# ASIC_1.net
KiCad netlist of a schematic drawn in Altium Designer
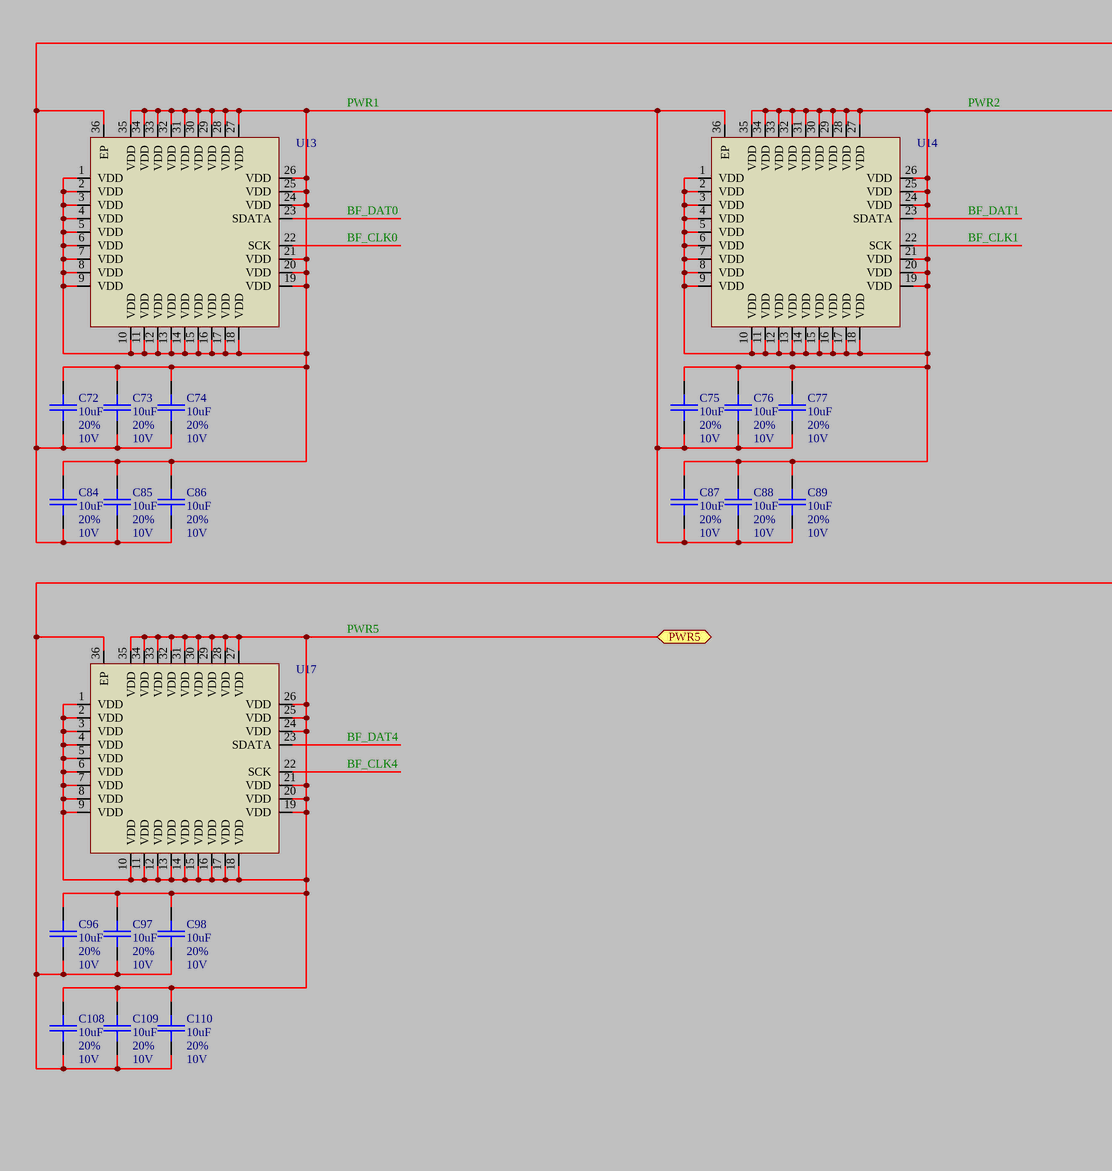
[diagram p0: ASIC_1.SchDoc, left]
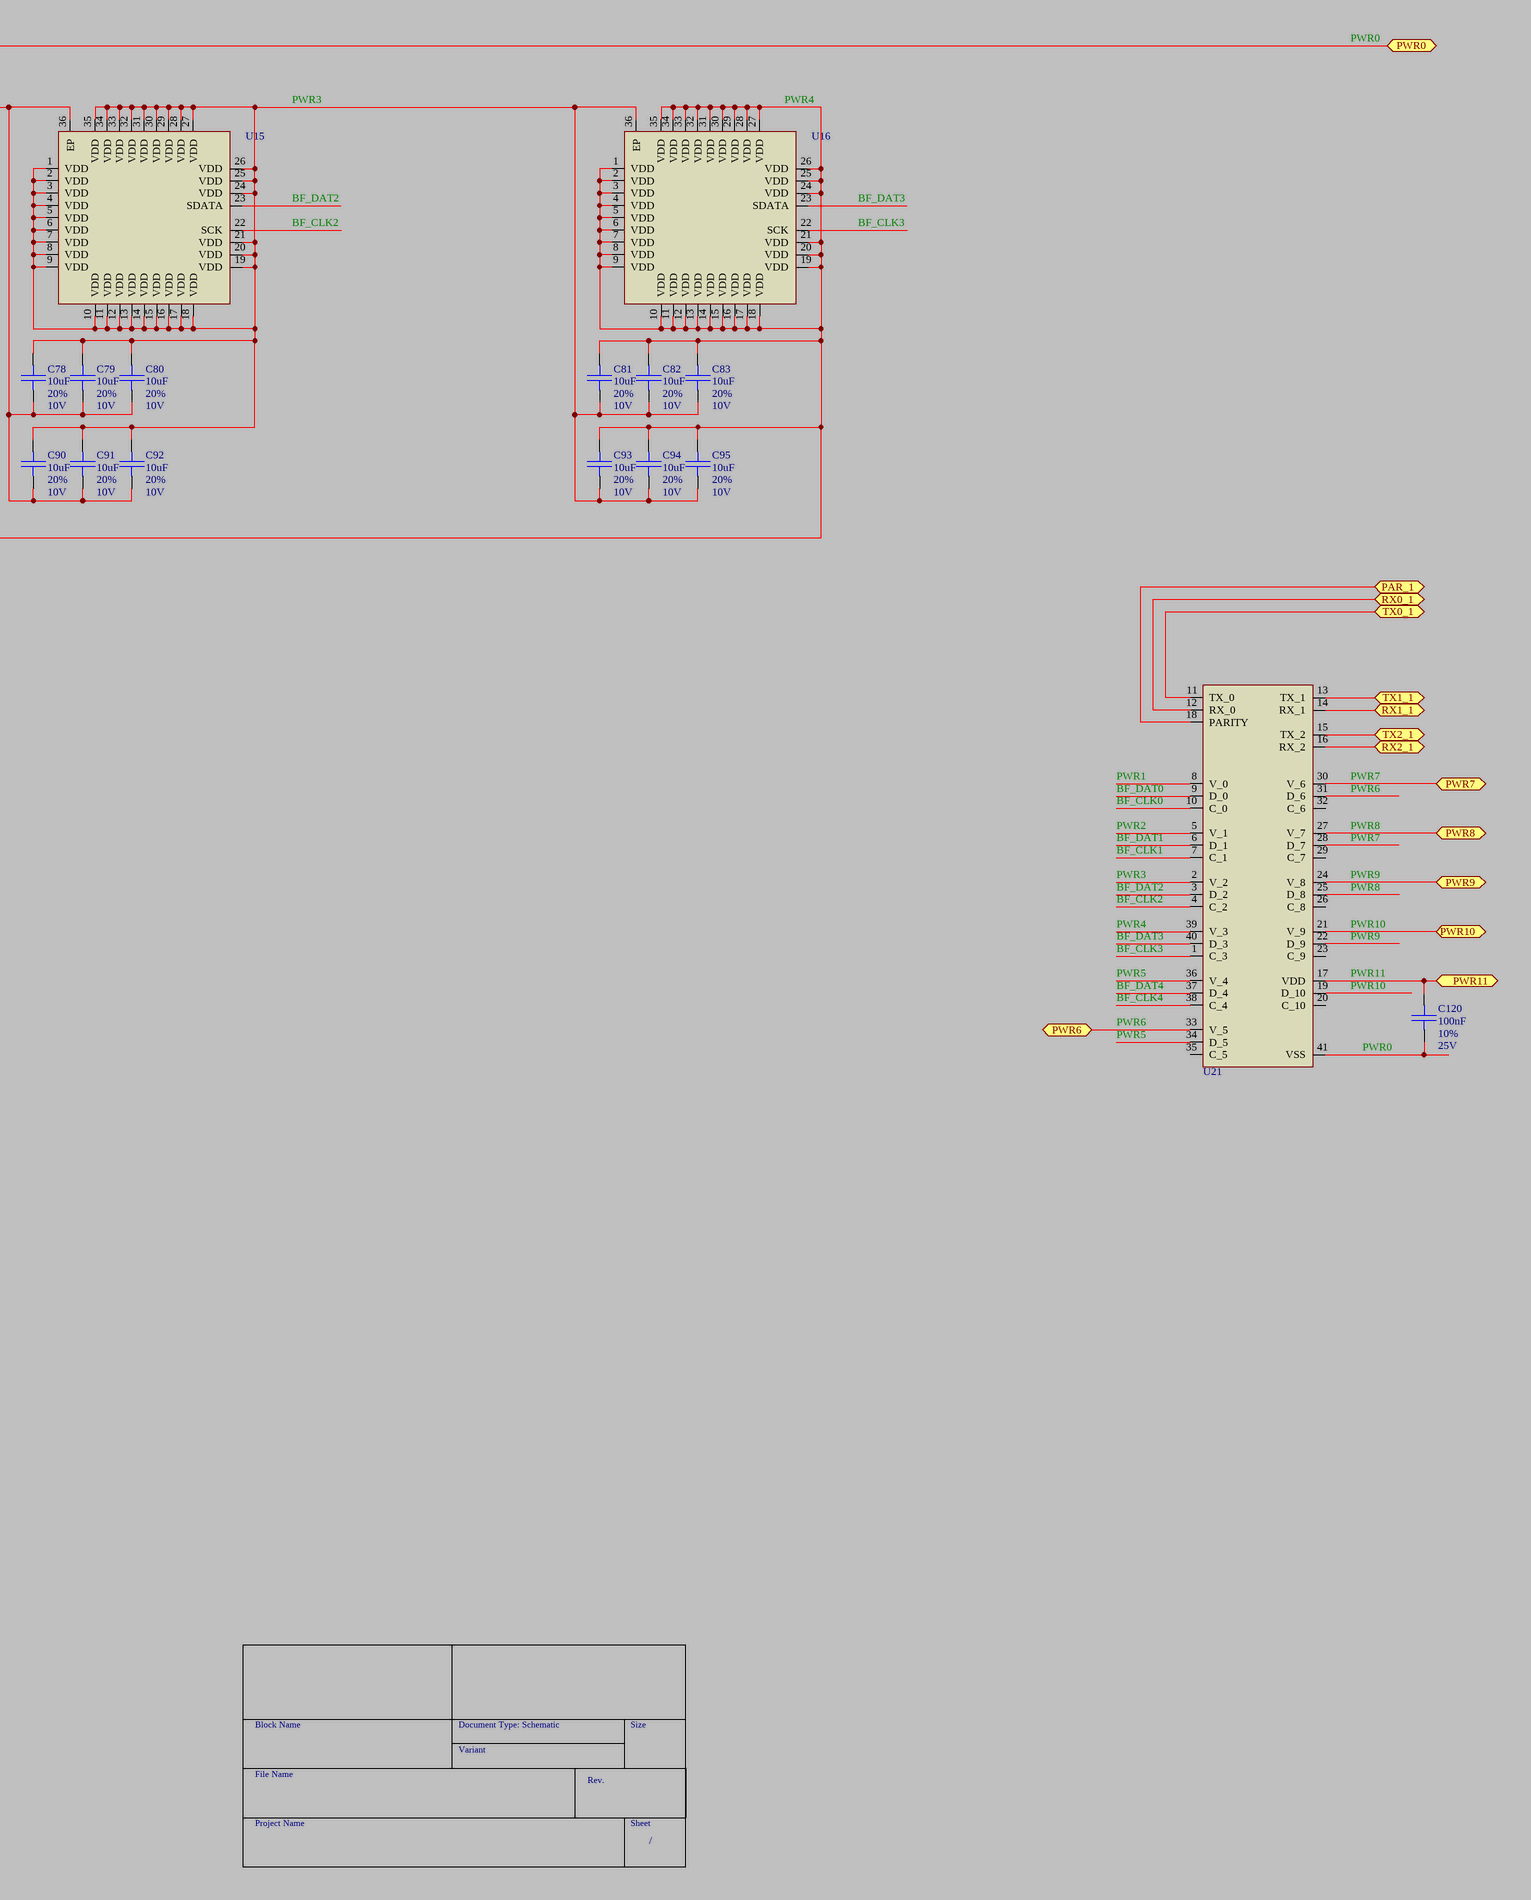
[diagram p1: ASIC_1.SchDoc, right]

(export (version "E")
  (design (tool "Eeschema 10.0.6"))
  (components
    (comp (ref "C72")
      (value "C")
      (footprint "SMD_0402_CAPC1005X70N")
      (fields
        (field (name "DB_PART_NUMBER") "CAP000047481")
        (field (name "DB_VALUE") "10uF")
        (field (name "DB_TOLERANCE") "20%")
        (field (name "DB_VOLTAGE") "10V")
        (field (name "DB_MANUFACTURER_PART") "SAMSUNG    CL05A106MP5NUNC")
        (field (name "DB_APPROVED_BY") "VSN")
      )
      (libsource (lib "Database_Libs1") (part "C"))
    )
    (comp (ref "C73")
      (value "C")
      (footprint "SMD_0402_CAPC1005X70N")
      (fields
        (field (name "DB_PART_NUMBER") "CAP000047481")
        (field (name "DB_VALUE") "10uF")
        (field (name "DB_TOLERANCE") "20%")
        (field (name "DB_VOLTAGE") "10V")
        (field (name "DB_MANUFACTURER_PART") "SAMSUNG    CL05A106MP5NUNC")
        (field (name "DB_APPROVED_BY") "VSN")
      )
      (libsource (lib "Database_Libs1") (part "C"))
    )
    (comp (ref "C74")
      (value "C")
      (footprint "SMD_0402_CAPC1005X70N")
      (fields
        (field (name "DB_PART_NUMBER") "CAP000047481")
        (field (name "DB_VALUE") "10uF")
        (field (name "DB_TOLERANCE") "20%")
        (field (name "DB_VOLTAGE") "10V")
        (field (name "DB_MANUFACTURER_PART") "SAMSUNG    CL05A106MP5NUNC")
        (field (name "DB_APPROVED_BY") "VSN")
      )
      (libsource (lib "Database_Libs1") (part "C"))
    )
    (comp (ref "C75")
      (value "C")
      (footprint "SMD_0402_CAPC1005X70N")
      (fields
        (field (name "DB_PART_NUMBER") "CAP000047481")
        (field (name "DB_VALUE") "10uF")
        (field (name "DB_TOLERANCE") "20%")
        (field (name "DB_VOLTAGE") "10V")
        (field (name "DB_MANUFACTURER_PART") "SAMSUNG    CL05A106MP5NUNC")
        (field (name "DB_APPROVED_BY") "VSN")
      )
      (libsource (lib "Database_Libs1") (part "C"))
    )
    (comp (ref "C76")
      (value "C")
      (footprint "SMD_0402_CAPC1005X70N")
      (fields
        (field (name "DB_PART_NUMBER") "CAP000047481")
        (field (name "DB_VALUE") "10uF")
        (field (name "DB_TOLERANCE") "20%")
        (field (name "DB_VOLTAGE") "10V")
        (field (name "DB_MANUFACTURER_PART") "SAMSUNG    CL05A106MP5NUNC")
        (field (name "DB_APPROVED_BY") "VSN")
      )
      (libsource (lib "Database_Libs1") (part "C"))
    )
    (comp (ref "C77")
      (value "C")
      (footprint "SMD_0402_CAPC1005X70N")
      (fields
        (field (name "DB_PART_NUMBER") "CAP000047481")
        (field (name "DB_VALUE") "10uF")
        (field (name "DB_TOLERANCE") "20%")
        (field (name "DB_VOLTAGE") "10V")
        (field (name "DB_MANUFACTURER_PART") "SAMSUNG    CL05A106MP5NUNC")
        (field (name "DB_APPROVED_BY") "VSN")
      )
      (libsource (lib "Database_Libs1") (part "C"))
    )
    (comp (ref "C78")
      (value "C")
      (footprint "SMD_0402_CAPC1005X70N")
      (fields
        (field (name "DB_PART_NUMBER") "CAP000047481")
        (field (name "DB_VALUE") "10uF")
        (field (name "DB_TOLERANCE") "20%")
        (field (name "DB_VOLTAGE") "10V")
        (field (name "DB_MANUFACTURER_PART") "SAMSUNG    CL05A106MP5NUNC")
        (field (name "DB_APPROVED_BY") "VSN")
      )
      (libsource (lib "Database_Libs1") (part "C"))
    )
    (comp (ref "C79")
      (value "C")
      (footprint "SMD_0402_CAPC1005X70N")
      (fields
        (field (name "DB_PART_NUMBER") "CAP000047481")
        (field (name "DB_VALUE") "10uF")
        (field (name "DB_TOLERANCE") "20%")
        (field (name "DB_VOLTAGE") "10V")
        (field (name "DB_MANUFACTURER_PART") "SAMSUNG    CL05A106MP5NUNC")
        (field (name "DB_APPROVED_BY") "VSN")
      )
      (libsource (lib "Database_Libs1") (part "C"))
    )
    (comp (ref "C80")
      (value "C")
      (footprint "SMD_0402_CAPC1005X70N")
      (fields
        (field (name "DB_PART_NUMBER") "CAP000047481")
        (field (name "DB_VALUE") "10uF")
        (field (name "DB_TOLERANCE") "20%")
        (field (name "DB_VOLTAGE") "10V")
        (field (name "DB_MANUFACTURER_PART") "SAMSUNG    CL05A106MP5NUNC")
        (field (name "DB_APPROVED_BY") "VSN")
      )
      (libsource (lib "Database_Libs1") (part "C"))
    )
    (comp (ref "C81")
      (value "C")
      (footprint "SMD_0402_CAPC1005X70N")
      (fields
        (field (name "DB_PART_NUMBER") "CAP000047481")
        (field (name "DB_VALUE") "10uF")
        (field (name "DB_TOLERANCE") "20%")
        (field (name "DB_VOLTAGE") "10V")
        (field (name "DB_MANUFACTURER_PART") "SAMSUNG    CL05A106MP5NUNC")
        (field (name "DB_APPROVED_BY") "VSN")
      )
      (libsource (lib "Database_Libs1") (part "C"))
    )
    (comp (ref "C82")
      (value "C")
      (footprint "SMD_0402_CAPC1005X70N")
      (fields
        (field (name "DB_PART_NUMBER") "CAP000047481")
        (field (name "DB_VALUE") "10uF")
        (field (name "DB_TOLERANCE") "20%")
        (field (name "DB_VOLTAGE") "10V")
        (field (name "DB_MANUFACTURER_PART") "SAMSUNG    CL05A106MP5NUNC")
        (field (name "DB_APPROVED_BY") "VSN")
      )
      (libsource (lib "Database_Libs1") (part "C"))
    )
    (comp (ref "C83")
      (value "C")
      (footprint "SMD_0402_CAPC1005X70N")
      (fields
        (field (name "DB_PART_NUMBER") "CAP000047481")
        (field (name "DB_VALUE") "10uF")
        (field (name "DB_TOLERANCE") "20%")
        (field (name "DB_VOLTAGE") "10V")
        (field (name "DB_MANUFACTURER_PART") "SAMSUNG    CL05A106MP5NUNC")
        (field (name "DB_APPROVED_BY") "VSN")
      )
      (libsource (lib "Database_Libs1") (part "C"))
    )
    (comp (ref "C84")
      (value "C")
      (footprint "SMD_0402_CAPC1005X70N")
      (fields
        (field (name "DB_PART_NUMBER") "CAP000047481")
        (field (name "DB_VALUE") "10uF")
        (field (name "DB_TOLERANCE") "20%")
        (field (name "DB_VOLTAGE") "10V")
        (field (name "DB_MANUFACTURER_PART") "SAMSUNG    CL05A106MP5NUNC")
        (field (name "DB_APPROVED_BY") "VSN")
      )
      (libsource (lib "Database_Libs1") (part "C"))
    )
    (comp (ref "C85")
      (value "C")
      (footprint "SMD_0402_CAPC1005X70N")
      (fields
        (field (name "DB_PART_NUMBER") "CAP000047481")
        (field (name "DB_VALUE") "10uF")
        (field (name "DB_TOLERANCE") "20%")
        (field (name "DB_VOLTAGE") "10V")
        (field (name "DB_MANUFACTURER_PART") "SAMSUNG    CL05A106MP5NUNC")
        (field (name "DB_APPROVED_BY") "VSN")
      )
      (libsource (lib "Database_Libs1") (part "C"))
    )
    (comp (ref "C86")
      (value "C")
      (footprint "SMD_0402_CAPC1005X70N")
      (fields
        (field (name "DB_PART_NUMBER") "CAP000047481")
        (field (name "DB_VALUE") "10uF")
        (field (name "DB_TOLERANCE") "20%")
        (field (name "DB_VOLTAGE") "10V")
        (field (name "DB_MANUFACTURER_PART") "SAMSUNG    CL05A106MP5NUNC")
        (field (name "DB_APPROVED_BY") "VSN")
      )
      (libsource (lib "Database_Libs1") (part "C"))
    )
    (comp (ref "C87")
      (value "C")
      (footprint "SMD_0402_CAPC1005X70N")
      (fields
        (field (name "DB_PART_NUMBER") "CAP000047481")
        (field (name "DB_VALUE") "10uF")
        (field (name "DB_TOLERANCE") "20%")
        (field (name "DB_VOLTAGE") "10V")
        (field (name "DB_MANUFACTURER_PART") "SAMSUNG    CL05A106MP5NUNC")
        (field (name "DB_APPROVED_BY") "VSN")
      )
      (libsource (lib "Database_Libs1") (part "C"))
    )
    (comp (ref "C88")
      (value "C")
      (footprint "SMD_0402_CAPC1005X70N")
      (fields
        (field (name "DB_PART_NUMBER") "CAP000047481")
        (field (name "DB_VALUE") "10uF")
        (field (name "DB_TOLERANCE") "20%")
        (field (name "DB_VOLTAGE") "10V")
        (field (name "DB_MANUFACTURER_PART") "SAMSUNG    CL05A106MP5NUNC")
        (field (name "DB_APPROVED_BY") "VSN")
      )
      (libsource (lib "Database_Libs1") (part "C"))
    )
    (comp (ref "C89")
      (value "C")
      (footprint "SMD_0402_CAPC1005X70N")
      (fields
        (field (name "DB_PART_NUMBER") "CAP000047481")
        (field (name "DB_VALUE") "10uF")
        (field (name "DB_TOLERANCE") "20%")
        (field (name "DB_VOLTAGE") "10V")
        (field (name "DB_MANUFACTURER_PART") "SAMSUNG    CL05A106MP5NUNC")
        (field (name "DB_APPROVED_BY") "VSN")
      )
      (libsource (lib "Database_Libs1") (part "C"))
    )
    (comp (ref "C90")
      (value "C")
      (footprint "SMD_0402_CAPC1005X70N")
      (fields
        (field (name "DB_PART_NUMBER") "CAP000047481")
        (field (name "DB_VALUE") "10uF")
        (field (name "DB_TOLERANCE") "20%")
        (field (name "DB_VOLTAGE") "10V")
        (field (name "DB_MANUFACTURER_PART") "SAMSUNG    CL05A106MP5NUNC")
        (field (name "DB_APPROVED_BY") "VSN")
      )
      (libsource (lib "Database_Libs1") (part "C"))
    )
    (comp (ref "C91")
      (value "C")
      (footprint "SMD_0402_CAPC1005X70N")
      (fields
        (field (name "DB_PART_NUMBER") "CAP000047481")
        (field (name "DB_VALUE") "10uF")
        (field (name "DB_TOLERANCE") "20%")
        (field (name "DB_VOLTAGE") "10V")
        (field (name "DB_MANUFACTURER_PART") "SAMSUNG    CL05A106MP5NUNC")
        (field (name "DB_APPROVED_BY") "VSN")
      )
      (libsource (lib "Database_Libs1") (part "C"))
    )
    (comp (ref "C92")
      (value "C")
      (footprint "SMD_0402_CAPC1005X70N")
      (fields
        (field (name "DB_PART_NUMBER") "CAP000047481")
        (field (name "DB_VALUE") "10uF")
        (field (name "DB_TOLERANCE") "20%")
        (field (name "DB_VOLTAGE") "10V")
        (field (name "DB_MANUFACTURER_PART") "SAMSUNG    CL05A106MP5NUNC")
        (field (name "DB_APPROVED_BY") "VSN")
      )
      (libsource (lib "Database_Libs1") (part "C"))
    )
    (comp (ref "C93")
      (value "C")
      (footprint "SMD_0402_CAPC1005X70N")
      (fields
        (field (name "DB_PART_NUMBER") "CAP000047481")
        (field (name "DB_VALUE") "10uF")
        (field (name "DB_TOLERANCE") "20%")
        (field (name "DB_VOLTAGE") "10V")
        (field (name "DB_MANUFACTURER_PART") "SAMSUNG    CL05A106MP5NUNC")
        (field (name "DB_APPROVED_BY") "VSN")
      )
      (libsource (lib "Database_Libs1") (part "C"))
    )
    (comp (ref "C94")
      (value "C")
      (footprint "SMD_0402_CAPC1005X70N")
      (fields
        (field (name "DB_PART_NUMBER") "CAP000047481")
        (field (name "DB_VALUE") "10uF")
        (field (name "DB_TOLERANCE") "20%")
        (field (name "DB_VOLTAGE") "10V")
        (field (name "DB_MANUFACTURER_PART") "SAMSUNG    CL05A106MP5NUNC")
        (field (name "DB_APPROVED_BY") "VSN")
      )
      (libsource (lib "Database_Libs1") (part "C"))
    )
    (comp (ref "C95")
      (value "C")
      (footprint "SMD_0402_CAPC1005X70N")
      (fields
        (field (name "DB_PART_NUMBER") "CAP000047481")
        (field (name "DB_VALUE") "10uF")
        (field (name "DB_TOLERANCE") "20%")
        (field (name "DB_VOLTAGE") "10V")
        (field (name "DB_MANUFACTURER_PART") "SAMSUNG    CL05A106MP5NUNC")
        (field (name "DB_APPROVED_BY") "VSN")
      )
      (libsource (lib "Database_Libs1") (part "C"))
    )
    (comp (ref "C96")
      (value "C")
      (footprint "SMD_0402_CAPC1005X70N")
      (fields
        (field (name "DB_PART_NUMBER") "CAP000047481")
        (field (name "DB_VALUE") "10uF")
        (field (name "DB_TOLERANCE") "20%")
        (field (name "DB_VOLTAGE") "10V")
        (field (name "DB_MANUFACTURER_PART") "SAMSUNG    CL05A106MP5NUNC")
        (field (name "DB_APPROVED_BY") "VSN")
      )
      (libsource (lib "Database_Libs1") (part "C"))
    )
    (comp (ref "C97")
      (value "C")
      (footprint "SMD_0402_CAPC1005X70N")
      (fields
        (field (name "DB_PART_NUMBER") "CAP000047481")
        (field (name "DB_VALUE") "10uF")
        (field (name "DB_TOLERANCE") "20%")
        (field (name "DB_VOLTAGE") "10V")
        (field (name "DB_MANUFACTURER_PART") "SAMSUNG    CL05A106MP5NUNC")
        (field (name "DB_APPROVED_BY") "VSN")
      )
      (libsource (lib "Database_Libs1") (part "C"))
    )
    (comp (ref "C98")
      (value "C")
      (footprint "SMD_0402_CAPC1005X70N")
      (fields
        (field (name "DB_PART_NUMBER") "CAP000047481")
        (field (name "DB_VALUE") "10uF")
        (field (name "DB_TOLERANCE") "20%")
        (field (name "DB_VOLTAGE") "10V")
        (field (name "DB_MANUFACTURER_PART") "SAMSUNG    CL05A106MP5NUNC")
        (field (name "DB_APPROVED_BY") "VSN")
      )
      (libsource (lib "Database_Libs1") (part "C"))
    )
    (comp (ref "C108")
      (value "C")
      (footprint "SMD_0402_CAPC1005X70N")
      (fields
        (field (name "DB_PART_NUMBER") "CAP000047481")
        (field (name "DB_VALUE") "10uF")
        (field (name "DB_TOLERANCE") "20%")
        (field (name "DB_VOLTAGE") "10V")
        (field (name "DB_MANUFACTURER_PART") "SAMSUNG    CL05A106MP5NUNC")
        (field (name "DB_APPROVED_BY") "VSN")
      )
      (libsource (lib "Database_Libs1") (part "C"))
    )
    (comp (ref "C109")
      (value "C")
      (footprint "SMD_0402_CAPC1005X70N")
      (fields
        (field (name "DB_PART_NUMBER") "CAP000047481")
        (field (name "DB_VALUE") "10uF")
        (field (name "DB_TOLERANCE") "20%")
        (field (name "DB_VOLTAGE") "10V")
        (field (name "DB_MANUFACTURER_PART") "SAMSUNG    CL05A106MP5NUNC")
        (field (name "DB_APPROVED_BY") "VSN")
      )
      (libsource (lib "Database_Libs1") (part "C"))
    )
    (comp (ref "C110")
      (value "C")
      (footprint "SMD_0402_CAPC1005X70N")
      (fields
        (field (name "DB_PART_NUMBER") "CAP000047481")
        (field (name "DB_VALUE") "10uF")
        (field (name "DB_TOLERANCE") "20%")
        (field (name "DB_VOLTAGE") "10V")
        (field (name "DB_MANUFACTURER_PART") "SAMSUNG    CL05A106MP5NUNC")
        (field (name "DB_APPROVED_BY") "VSN")
      )
      (libsource (lib "Database_Libs1") (part "C"))
    )
    (comp (ref "C120")
      (value "C")
      (footprint "SMD_0402_CAPC1005X55N")
      (fields
        (field (name "DB_PART_NUMBER") "CAP000047469")
        (field (name "DB_VALUE") "100nF")
        (field (name "DB_TOLERANCE") "10%")
        (field (name "DB_VOLTAGE") "25V")
        (field (name "DB_MANUFACTURER_PART") "SAMSUNG    CL05A104KA5NNNC")
        (field (name "DB_APPROVED_BY") "VSN")
      )
      (libsource (lib "Database_Libs1") (part "C"))
    )
    (comp (ref "U13")
      (value "IC_BITFURY16")
      (footprint "SMD_QFN50P600X600X175-36AN")
      (description "BitFury 2016 16 nm")
      (libsource (lib "BitCoin") (part "IC_BITFURY16"))
    )
    (comp (ref "U14")
      (value "IC_BITFURY16")
      (footprint "SMD_QFN50P600X600X175-36AN")
      (description "BitFury 2016 16 nm")
      (libsource (lib "BitCoin") (part "IC_BITFURY16"))
    )
    (comp (ref "U15")
      (value "IC_BITFURY16")
      (footprint "SMD_QFN50P600X600X175-36AN")
      (description "BitFury 2016 16 nm")
      (libsource (lib "BitCoin") (part "IC_BITFURY16"))
    )
    (comp (ref "U16")
      (value "IC_BITFURY16")
      (footprint "SMD_QFN50P600X600X175-36AN")
      (description "BitFury 2016 16 nm")
      (libsource (lib "BitCoin") (part "IC_BITFURY16"))
    )
    (comp (ref "U17")
      (value "IC_BITFURY16")
      (footprint "SMD_QFN50P600X600X175-36AN")
      (description "BitFury 2016 16 nm")
      (libsource (lib "BitCoin") (part "IC_BITFURY16"))
    )
    (comp (ref "U21")
      (value "IC_BTC250")
      (footprint "SMD_QFN40P500X500X80-41N")
      (libsource (lib "BitCoin") (part "IC_BTC250"))
    )
  )
  (nets
    (net (code "1") (name "/BF_CLK0") (class "Default")
      (node (ref "U13") (pin "22") (pinfunction "SCK_22") (pintype "passive"))
      (node (ref "U21") (pin "10") (pinfunction "C_0_10") (pintype "passive"))
    )
    (net (code "2") (name "/BF_CLK1") (class "Default")
      (node (ref "U14") (pin "22") (pinfunction "SCK_22") (pintype "passive"))
      (node (ref "U21") (pin "7") (pinfunction "C_1_7") (pintype "passive"))
    )
    (net (code "3") (name "/BF_CLK2") (class "Default")
      (node (ref "U15") (pin "22") (pinfunction "SCK_22") (pintype "passive"))
      (node (ref "U21") (pin "4") (pinfunction "C_2_4") (pintype "passive"))
    )
    (net (code "4") (name "/BF_CLK3") (class "Default")
      (node (ref "U16") (pin "22") (pinfunction "SCK_22") (pintype "passive"))
      (node (ref "U21") (pin "1") (pinfunction "C_3_1") (pintype "passive"))
    )
    (net (code "5") (name "/BF_CLK4") (class "Default")
      (node (ref "U17") (pin "22") (pinfunction "SCK_22") (pintype "passive"))
      (node (ref "U21") (pin "38") (pinfunction "C_4_38") (pintype "passive"))
    )
    (net (code "6") (name "/BF_DAT0") (class "Default")
      (node (ref "U13") (pin "23") (pinfunction "SDATA_23") (pintype "passive"))
      (node (ref "U21") (pin "9") (pinfunction "D_0_9") (pintype "passive"))
    )
    (net (code "7") (name "/BF_DAT1") (class "Default")
      (node (ref "U14") (pin "23") (pinfunction "SDATA_23") (pintype "passive"))
      (node (ref "U21") (pin "6") (pinfunction "D_1_6") (pintype "passive"))
    )
    (net (code "8") (name "/BF_DAT2") (class "Default")
      (node (ref "U15") (pin "23") (pinfunction "SDATA_23") (pintype "passive"))
      (node (ref "U21") (pin "3") (pinfunction "D_2_3") (pintype "passive"))
    )
    (net (code "9") (name "/BF_DAT3") (class "Default")
      (node (ref "U16") (pin "23") (pinfunction "SDATA_23") (pintype "passive"))
      (node (ref "U21") (pin "40") (pinfunction "D_3_40") (pintype "passive"))
    )
    (net (code "10") (name "/BF_DAT4") (class "Default")
      (node (ref "U17") (pin "23") (pinfunction "SDATA_23") (pintype "passive"))
      (node (ref "U21") (pin "37") (pinfunction "D_4_37") (pintype "passive"))
    )
    (net (code "11") (name "/PAR_1") (class "Default")
      (node (ref "U21") (pin "18") (pinfunction "PARITY_18") (pintype "passive"))
    )
    (net (code "12") (name "/PWR0") (class "Default")
      (node (ref "C120") (pin "2") (pinfunction "2_2") (pintype "passive"))
      (node (ref "C72") (pin "2") (pinfunction "2_2") (pintype "passive"))
      (node (ref "C73") (pin "2") (pinfunction "2_2") (pintype "passive"))
      (node (ref "C74") (pin "2") (pinfunction "2_2") (pintype "passive"))
      (node (ref "C84") (pin "2") (pinfunction "2_2") (pintype "passive"))
      (node (ref "C85") (pin "2") (pinfunction "2_2") (pintype "passive"))
      (node (ref "C86") (pin "2") (pinfunction "2_2") (pintype "passive"))
      (node (ref "U13") (pin "36") (pinfunction "EP_36") (pintype "passive"))
      (node (ref "U21") (pin "41") (pinfunction "VSS_41") (pintype "passive"))
    )
    (net (code "13") (name "/PWR1") (class "Default")
      (node (ref "C72") (pin "1") (pinfunction "1_1") (pintype "passive"))
      (node (ref "C73") (pin "1") (pinfunction "1_1") (pintype "passive"))
      (node (ref "C74") (pin "1") (pinfunction "1_1") (pintype "passive"))
      (node (ref "C75") (pin "2") (pinfunction "2_2") (pintype "passive"))
      (node (ref "C76") (pin "2") (pinfunction "2_2") (pintype "passive"))
      (node (ref "C77") (pin "2") (pinfunction "2_2") (pintype "passive"))
      (node (ref "C84") (pin "1") (pinfunction "1_1") (pintype "passive"))
      (node (ref "C85") (pin "1") (pinfunction "1_1") (pintype "passive"))
      (node (ref "C86") (pin "1") (pinfunction "1_1") (pintype "passive"))
      (node (ref "C87") (pin "2") (pinfunction "2_2") (pintype "passive"))
      (node (ref "C88") (pin "2") (pinfunction "2_2") (pintype "passive"))
      (node (ref "C89") (pin "2") (pinfunction "2_2") (pintype "passive"))
      (node (ref "U13") (pin "1") (pinfunction "VDD_1") (pintype "passive"))
      (node (ref "U13") (pin "10") (pinfunction "VDD_10") (pintype "passive"))
      (node (ref "U13") (pin "11") (pinfunction "VDD_11") (pintype "passive"))
      (node (ref "U13") (pin "12") (pinfunction "VDD_12") (pintype "passive"))
      (node (ref "U13") (pin "13") (pinfunction "VDD_13") (pintype "passive"))
      (node (ref "U13") (pin "14") (pinfunction "VDD_14") (pintype "passive"))
      (node (ref "U13") (pin "15") (pinfunction "VDD_15") (pintype "passive"))
      (node (ref "U13") (pin "16") (pinfunction "VDD_16") (pintype "passive"))
      (node (ref "U13") (pin "17") (pinfunction "VDD_17") (pintype "passive"))
      (node (ref "U13") (pin "18") (pinfunction "VDD_18") (pintype "passive"))
      (node (ref "U13") (pin "19") (pinfunction "VDD_19") (pintype "passive"))
      (node (ref "U13") (pin "2") (pinfunction "VDD_2") (pintype "passive"))
      (node (ref "U13") (pin "20") (pinfunction "VDD_20") (pintype "passive"))
      (node (ref "U13") (pin "21") (pinfunction "VDD_21") (pintype "passive"))
      (node (ref "U13") (pin "24") (pinfunction "VDD_24") (pintype "passive"))
      (node (ref "U13") (pin "25") (pinfunction "VDD_25") (pintype "passive"))
      (node (ref "U13") (pin "26") (pinfunction "VDD_26") (pintype "passive"))
      (node (ref "U13") (pin "27") (pinfunction "VDD_27") (pintype "passive"))
      (node (ref "U13") (pin "28") (pinfunction "VDD_28") (pintype "passive"))
      (node (ref "U13") (pin "29") (pinfunction "VDD_29") (pintype "passive"))
      (node (ref "U13") (pin "3") (pinfunction "VDD_3") (pintype "passive"))
      (node (ref "U13") (pin "30") (pinfunction "VDD_30") (pintype "passive"))
      (node (ref "U13") (pin "31") (pinfunction "VDD_31") (pintype "passive"))
      (node (ref "U13") (pin "32") (pinfunction "VDD_32") (pintype "passive"))
      (node (ref "U13") (pin "33") (pinfunction "VDD_33") (pintype "passive"))
      (node (ref "U13") (pin "34") (pinfunction "VDD_34") (pintype "passive"))
      (node (ref "U13") (pin "35") (pinfunction "VDD_35") (pintype "passive"))
      (node (ref "U13") (pin "4") (pinfunction "VDD_4") (pintype "passive"))
      (node (ref "U13") (pin "5") (pinfunction "VDD_5") (pintype "passive"))
      (node (ref "U13") (pin "6") (pinfunction "VDD_6") (pintype "passive"))
      (node (ref "U13") (pin "7") (pinfunction "VDD_7") (pintype "passive"))
      (node (ref "U13") (pin "8") (pinfunction "VDD_8") (pintype "passive"))
      (node (ref "U13") (pin "9") (pinfunction "VDD_9") (pintype "passive"))
      (node (ref "U14") (pin "36") (pinfunction "EP_36") (pintype "passive"))
      (node (ref "U21") (pin "8") (pinfunction "V_0_8") (pintype "passive"))
    )
    (net (code "14") (name "/PWR2") (class "Default")
      (node (ref "C75") (pin "1") (pinfunction "1_1") (pintype "passive"))
      (node (ref "C76") (pin "1") (pinfunction "1_1") (pintype "passive"))
      (node (ref "C77") (pin "1") (pinfunction "1_1") (pintype "passive"))
      (node (ref "C78") (pin "2") (pinfunction "2_2") (pintype "passive"))
      (node (ref "C79") (pin "2") (pinfunction "2_2") (pintype "passive"))
      (node (ref "C80") (pin "2") (pinfunction "2_2") (pintype "passive"))
      (node (ref "C87") (pin "1") (pinfunction "1_1") (pintype "passive"))
      (node (ref "C88") (pin "1") (pinfunction "1_1") (pintype "passive"))
      (node (ref "C89") (pin "1") (pinfunction "1_1") (pintype "passive"))
      (node (ref "C90") (pin "2") (pinfunction "2_2") (pintype "passive"))
      (node (ref "C91") (pin "2") (pinfunction "2_2") (pintype "passive"))
      (node (ref "C92") (pin "2") (pinfunction "2_2") (pintype "passive"))
      (node (ref "U14") (pin "1") (pinfunction "VDD_1") (pintype "passive"))
      (node (ref "U14") (pin "10") (pinfunction "VDD_10") (pintype "passive"))
      (node (ref "U14") (pin "11") (pinfunction "VDD_11") (pintype "passive"))
      (node (ref "U14") (pin "12") (pinfunction "VDD_12") (pintype "passive"))
      (node (ref "U14") (pin "13") (pinfunction "VDD_13") (pintype "passive"))
      (node (ref "U14") (pin "14") (pinfunction "VDD_14") (pintype "passive"))
      (node (ref "U14") (pin "15") (pinfunction "VDD_15") (pintype "passive"))
      (node (ref "U14") (pin "16") (pinfunction "VDD_16") (pintype "passive"))
      (node (ref "U14") (pin "17") (pinfunction "VDD_17") (pintype "passive"))
      (node (ref "U14") (pin "18") (pinfunction "VDD_18") (pintype "passive"))
      (node (ref "U14") (pin "19") (pinfunction "VDD_19") (pintype "passive"))
      (node (ref "U14") (pin "2") (pinfunction "VDD_2") (pintype "passive"))
      (node (ref "U14") (pin "20") (pinfunction "VDD_20") (pintype "passive"))
      (node (ref "U14") (pin "21") (pinfunction "VDD_21") (pintype "passive"))
      (node (ref "U14") (pin "24") (pinfunction "VDD_24") (pintype "passive"))
      (node (ref "U14") (pin "25") (pinfunction "VDD_25") (pintype "passive"))
      (node (ref "U14") (pin "26") (pinfunction "VDD_26") (pintype "passive"))
      (node (ref "U14") (pin "27") (pinfunction "VDD_27") (pintype "passive"))
      (node (ref "U14") (pin "28") (pinfunction "VDD_28") (pintype "passive"))
      (node (ref "U14") (pin "29") (pinfunction "VDD_29") (pintype "passive"))
      (node (ref "U14") (pin "3") (pinfunction "VDD_3") (pintype "passive"))
      (node (ref "U14") (pin "30") (pinfunction "VDD_30") (pintype "passive"))
      (node (ref "U14") (pin "31") (pinfunction "VDD_31") (pintype "passive"))
      (node (ref "U14") (pin "32") (pinfunction "VDD_32") (pintype "passive"))
      (node (ref "U14") (pin "33") (pinfunction "VDD_33") (pintype "passive"))
      (node (ref "U14") (pin "34") (pinfunction "VDD_34") (pintype "passive"))
      (node (ref "U14") (pin "35") (pinfunction "VDD_35") (pintype "passive"))
      (node (ref "U14") (pin "4") (pinfunction "VDD_4") (pintype "passive"))
      (node (ref "U14") (pin "5") (pinfunction "VDD_5") (pintype "passive"))
      (node (ref "U14") (pin "6") (pinfunction "VDD_6") (pintype "passive"))
      (node (ref "U14") (pin "7") (pinfunction "VDD_7") (pintype "passive"))
      (node (ref "U14") (pin "8") (pinfunction "VDD_8") (pintype "passive"))
      (node (ref "U14") (pin "9") (pinfunction "VDD_9") (pintype "passive"))
      (node (ref "U15") (pin "36") (pinfunction "EP_36") (pintype "passive"))
      (node (ref "U21") (pin "5") (pinfunction "V_1_5") (pintype "passive"))
    )
    (net (code "15") (name "/PWR3") (class "Default")
      (node (ref "C78") (pin "1") (pinfunction "1_1") (pintype "passive"))
      (node (ref "C79") (pin "1") (pinfunction "1_1") (pintype "passive"))
      (node (ref "C80") (pin "1") (pinfunction "1_1") (pintype "passive"))
      (node (ref "C81") (pin "2") (pinfunction "2_2") (pintype "passive"))
      (node (ref "C82") (pin "2") (pinfunction "2_2") (pintype "passive"))
      (node (ref "C83") (pin "2") (pinfunction "2_2") (pintype "passive"))
      (node (ref "C90") (pin "1") (pinfunction "1_1") (pintype "passive"))
      (node (ref "C91") (pin "1") (pinfunction "1_1") (pintype "passive"))
      (node (ref "C92") (pin "1") (pinfunction "1_1") (pintype "passive"))
      (node (ref "C93") (pin "2") (pinfunction "2_2") (pintype "passive"))
      (node (ref "C94") (pin "2") (pinfunction "2_2") (pintype "passive"))
      (node (ref "C95") (pin "2") (pinfunction "2_2") (pintype "passive"))
      (node (ref "U15") (pin "1") (pinfunction "VDD_1") (pintype "passive"))
      (node (ref "U15") (pin "10") (pinfunction "VDD_10") (pintype "passive"))
      (node (ref "U15") (pin "11") (pinfunction "VDD_11") (pintype "passive"))
      (node (ref "U15") (pin "12") (pinfunction "VDD_12") (pintype "passive"))
      (node (ref "U15") (pin "13") (pinfunction "VDD_13") (pintype "passive"))
      (node (ref "U15") (pin "14") (pinfunction "VDD_14") (pintype "passive"))
      (node (ref "U15") (pin "15") (pinfunction "VDD_15") (pintype "passive"))
      (node (ref "U15") (pin "16") (pinfunction "VDD_16") (pintype "passive"))
      (node (ref "U15") (pin "17") (pinfunction "VDD_17") (pintype "passive"))
      (node (ref "U15") (pin "18") (pinfunction "VDD_18") (pintype "passive"))
      (node (ref "U15") (pin "19") (pinfunction "VDD_19") (pintype "passive"))
      (node (ref "U15") (pin "2") (pinfunction "VDD_2") (pintype "passive"))
      (node (ref "U15") (pin "20") (pinfunction "VDD_20") (pintype "passive"))
      (node (ref "U15") (pin "21") (pinfunction "VDD_21") (pintype "passive"))
      (node (ref "U15") (pin "24") (pinfunction "VDD_24") (pintype "passive"))
      (node (ref "U15") (pin "25") (pinfunction "VDD_25") (pintype "passive"))
      (node (ref "U15") (pin "26") (pinfunction "VDD_26") (pintype "passive"))
      (node (ref "U15") (pin "27") (pinfunction "VDD_27") (pintype "passive"))
      (node (ref "U15") (pin "28") (pinfunction "VDD_28") (pintype "passive"))
      (node (ref "U15") (pin "29") (pinfunction "VDD_29") (pintype "passive"))
      (node (ref "U15") (pin "3") (pinfunction "VDD_3") (pintype "passive"))
      (node (ref "U15") (pin "30") (pinfunction "VDD_30") (pintype "passive"))
      (node (ref "U15") (pin "31") (pinfunction "VDD_31") (pintype "passive"))
      (node (ref "U15") (pin "32") (pinfunction "VDD_32") (pintype "passive"))
      (node (ref "U15") (pin "33") (pinfunction "VDD_33") (pintype "passive"))
      (node (ref "U15") (pin "34") (pinfunction "VDD_34") (pintype "passive"))
      (node (ref "U15") (pin "35") (pinfunction "VDD_35") (pintype "passive"))
      (node (ref "U15") (pin "4") (pinfunction "VDD_4") (pintype "passive"))
      (node (ref "U15") (pin "5") (pinfunction "VDD_5") (pintype "passive"))
      (node (ref "U15") (pin "6") (pinfunction "VDD_6") (pintype "passive"))
      (node (ref "U15") (pin "7") (pinfunction "VDD_7") (pintype "passive"))
      (node (ref "U15") (pin "8") (pinfunction "VDD_8") (pintype "passive"))
      (node (ref "U15") (pin "9") (pinfunction "VDD_9") (pintype "passive"))
      (node (ref "U16") (pin "36") (pinfunction "EP_36") (pintype "passive"))
      (node (ref "U21") (pin "2") (pinfunction "V_2_2") (pintype "passive"))
    )
    (net (code "16") (name "/PWR4") (class "Default")
      (node (ref "C108") (pin "2") (pinfunction "2_2") (pintype "passive"))
      (node (ref "C109") (pin "2") (pinfunction "2_2") (pintype "passive"))
      (node (ref "C110") (pin "2") (pinfunction "2_2") (pintype "passive"))
      (node (ref "C81") (pin "1") (pinfunction "1_1") (pintype "passive"))
      (node (ref "C82") (pin "1") (pinfunction "1_1") (pintype "passive"))
      (node (ref "C83") (pin "1") (pinfunction "1_1") (pintype "passive"))
      (node (ref "C93") (pin "1") (pinfunction "1_1") (pintype "passive"))
      (node (ref "C94") (pin "1") (pinfunction "1_1") (pintype "passive"))
      (node (ref "C95") (pin "1") (pinfunction "1_1") (pintype "passive"))
      (node (ref "C96") (pin "2") (pinfunction "2_2") (pintype "passive"))
      (node (ref "C97") (pin "2") (pinfunction "2_2") (pintype "passive"))
      (node (ref "C98") (pin "2") (pinfunction "2_2") (pintype "passive"))
      (node (ref "U16") (pin "1") (pinfunction "VDD_1") (pintype "passive"))
      (node (ref "U16") (pin "10") (pinfunction "VDD_10") (pintype "passive"))
      (node (ref "U16") (pin "11") (pinfunction "VDD_11") (pintype "passive"))
      (node (ref "U16") (pin "12") (pinfunction "VDD_12") (pintype "passive"))
      (node (ref "U16") (pin "13") (pinfunction "VDD_13") (pintype "passive"))
      (node (ref "U16") (pin "14") (pinfunction "VDD_14") (pintype "passive"))
      (node (ref "U16") (pin "15") (pinfunction "VDD_15") (pintype "passive"))
      (node (ref "U16") (pin "16") (pinfunction "VDD_16") (pintype "passive"))
      (node (ref "U16") (pin "17") (pinfunction "VDD_17") (pintype "passive"))
      (node (ref "U16") (pin "18") (pinfunction "VDD_18") (pintype "passive"))
      (node (ref "U16") (pin "19") (pinfunction "VDD_19") (pintype "passive"))
      (node (ref "U16") (pin "2") (pinfunction "VDD_2") (pintype "passive"))
      (node (ref "U16") (pin "20") (pinfunction "VDD_20") (pintype "passive"))
      (node (ref "U16") (pin "21") (pinfunction "VDD_21") (pintype "passive"))
      (node (ref "U16") (pin "24") (pinfunction "VDD_24") (pintype "passive"))
      (node (ref "U16") (pin "25") (pinfunction "VDD_25") (pintype "passive"))
      (node (ref "U16") (pin "26") (pinfunction "VDD_26") (pintype "passive"))
      (node (ref "U16") (pin "27") (pinfunction "VDD_27") (pintype "passive"))
      (node (ref "U16") (pin "28") (pinfunction "VDD_28") (pintype "passive"))
      (node (ref "U16") (pin "29") (pinfunction "VDD_29") (pintype "passive"))
      (node (ref "U16") (pin "3") (pinfunction "VDD_3") (pintype "passive"))
      (node (ref "U16") (pin "30") (pinfunction "VDD_30") (pintype "passive"))
      (node (ref "U16") (pin "31") (pinfunction "VDD_31") (pintype "passive"))
      (node (ref "U16") (pin "32") (pinfunction "VDD_32") (pintype "passive"))
      (node (ref "U16") (pin "33") (pinfunction "VDD_33") (pintype "passive"))
      (node (ref "U16") (pin "34") (pinfunction "VDD_34") (pintype "passive"))
      (node (ref "U16") (pin "35") (pinfunction "VDD_35") (pintype "passive"))
      (node (ref "U16") (pin "4") (pinfunction "VDD_4") (pintype "passive"))
      (node (ref "U16") (pin "5") (pinfunction "VDD_5") (pintype "passive"))
      (node (ref "U16") (pin "6") (pinfunction "VDD_6") (pintype "passive"))
      (node (ref "U16") (pin "7") (pinfunction "VDD_7") (pintype "passive"))
      (node (ref "U16") (pin "8") (pinfunction "VDD_8") (pintype "passive"))
      (node (ref "U16") (pin "9") (pinfunction "VDD_9") (pintype "passive"))
      (node (ref "U17") (pin "36") (pinfunction "EP_36") (pintype "passive"))
      (node (ref "U21") (pin "39") (pinfunction "V_3_39") (pintype "passive"))
    )
    (net (code "17") (name "/PWR5") (class "Default")
      (node (ref "C108") (pin "1") (pinfunction "1_1") (pintype "passive"))
      (node (ref "C109") (pin "1") (pinfunction "1_1") (pintype "passive"))
      (node (ref "C110") (pin "1") (pinfunction "1_1") (pintype "passive"))
      (node (ref "C96") (pin "1") (pinfunction "1_1") (pintype "passive"))
      (node (ref "C97") (pin "1") (pinfunction "1_1") (pintype "passive"))
      (node (ref "C98") (pin "1") (pinfunction "1_1") (pintype "passive"))
      (node (ref "U17") (pin "1") (pinfunction "VDD_1") (pintype "passive"))
      (node (ref "U17") (pin "10") (pinfunction "VDD_10") (pintype "passive"))
      (node (ref "U17") (pin "11") (pinfunction "VDD_11") (pintype "passive"))
      (node (ref "U17") (pin "12") (pinfunction "VDD_12") (pintype "passive"))
      (node (ref "U17") (pin "13") (pinfunction "VDD_13") (pintype "passive"))
      (node (ref "U17") (pin "14") (pinfunction "VDD_14") (pintype "passive"))
      (node (ref "U17") (pin "15") (pinfunction "VDD_15") (pintype "passive"))
      (node (ref "U17") (pin "16") (pinfunction "VDD_16") (pintype "passive"))
      (node (ref "U17") (pin "17") (pinfunction "VDD_17") (pintype "passive"))
      (node (ref "U17") (pin "18") (pinfunction "VDD_18") (pintype "passive"))
      (node (ref "U17") (pin "19") (pinfunction "VDD_19") (pintype "passive"))
      (node (ref "U17") (pin "2") (pinfunction "VDD_2") (pintype "passive"))
      (node (ref "U17") (pin "20") (pinfunction "VDD_20") (pintype "passive"))
      (node (ref "U17") (pin "21") (pinfunction "VDD_21") (pintype "passive"))
      (node (ref "U17") (pin "24") (pinfunction "VDD_24") (pintype "passive"))
      (node (ref "U17") (pin "25") (pinfunction "VDD_25") (pintype "passive"))
      (node (ref "U17") (pin "26") (pinfunction "VDD_26") (pintype "passive"))
      (node (ref "U17") (pin "27") (pinfunction "VDD_27") (pintype "passive"))
      (node (ref "U17") (pin "28") (pinfunction "VDD_28") (pintype "passive"))
      (node (ref "U17") (pin "29") (pinfunction "VDD_29") (pintype "passive"))
      (node (ref "U17") (pin "3") (pinfunction "VDD_3") (pintype "passive"))
      (node (ref "U17") (pin "30") (pinfunction "VDD_30") (pintype "passive"))
      (node (ref "U17") (pin "31") (pinfunction "VDD_31") (pintype "passive"))
      (node (ref "U17") (pin "32") (pinfunction "VDD_32") (pintype "passive"))
      (node (ref "U17") (pin "33") (pinfunction "VDD_33") (pintype "passive"))
      (node (ref "U17") (pin "34") (pinfunction "VDD_34") (pintype "passive"))
      (node (ref "U17") (pin "35") (pinfunction "VDD_35") (pintype "passive"))
      (node (ref "U17") (pin "4") (pinfunction "VDD_4") (pintype "passive"))
      (node (ref "U17") (pin "5") (pinfunction "VDD_5") (pintype "passive"))
      (node (ref "U17") (pin "6") (pinfunction "VDD_6") (pintype "passive"))
      (node (ref "U17") (pin "7") (pinfunction "VDD_7") (pintype "passive"))
      (node (ref "U17") (pin "8") (pinfunction "VDD_8") (pintype "passive"))
      (node (ref "U17") (pin "9") (pinfunction "VDD_9") (pintype "passive"))
      (node (ref "U21") (pin "34") (pinfunction "D_5_34") (pintype "passive"))
      (node (ref "U21") (pin "36") (pinfunction "V_4_36") (pintype "passive"))
    )
    (net (code "18") (name "/PWR6") (class "Default")
      (node (ref "U21") (pin "31") (pinfunction "D_6_31") (pintype "passive"))
      (node (ref "U21") (pin "33") (pinfunction "V_5_33") (pintype "passive"))
    )
    (net (code "19") (name "/PWR7") (class "Default")
      (node (ref "U21") (pin "28") (pinfunction "D_7_28") (pintype "passive"))
      (node (ref "U21") (pin "30") (pinfunction "V_6_30") (pintype "passive"))
    )
    (net (code "20") (name "/PWR8") (class "Default")
      (node (ref "U21") (pin "25") (pinfunction "D_8_25") (pintype "passive"))
      (node (ref "U21") (pin "27") (pinfunction "V_7_27") (pintype "passive"))
    )
    (net (code "21") (name "/PWR9") (class "Default")
      (node (ref "U21") (pin "22") (pinfunction "D_9_22") (pintype "passive"))
      (node (ref "U21") (pin "24") (pinfunction "V_8_24") (pintype "passive"))
    )
    (net (code "22") (name "/PWR10") (class "Default")
      (node (ref "U21") (pin "19") (pinfunction "D_10_19") (pintype "passive"))
      (node (ref "U21") (pin "21") (pinfunction "V_9_21") (pintype "passive"))
    )
    (net (code "23") (name "/PWR11") (class "Default")
      (node (ref "C120") (pin "1") (pinfunction "1_1") (pintype "passive"))
      (node (ref "U21") (pin "17") (pinfunction "VDD_17") (pintype "passive"))
    )
    (net (code "24") (name "/RX0_1") (class "Default")
      (node (ref "U21") (pin "12") (pinfunction "RX_0_12") (pintype "passive"))
    )
    (net (code "25") (name "/RX1_1") (class "Default")
      (node (ref "U21") (pin "14") (pinfunction "RX_1_14") (pintype "passive"))
    )
    (net (code "26") (name "/RX2_1") (class "Default")
      (node (ref "U21") (pin "16") (pinfunction "RX_2_16") (pintype "passive"))
    )
    (net (code "27") (name "/TX0_1") (class "Default")
      (node (ref "U21") (pin "11") (pinfunction "TX_0_11") (pintype "passive"))
    )
    (net (code "28") (name "/TX1_1") (class "Default")
      (node (ref "U21") (pin "13") (pinfunction "TX_1_13") (pintype "passive"))
    )
    (net (code "29") (name "/TX2_1") (class "Default")
      (node (ref "U21") (pin "15") (pinfunction "TX_2_15") (pintype "passive"))
    )
    (net (code "30") (name "unconnected-(U21-C_5-Pad35)") (class "Default")
      (node (ref "U21") (pin "35") (pinfunction "C_5_35") (pintype "passive"))
    )
    (net (code "31") (name "unconnected-(U21-C_6-Pad32)") (class "Default")
      (node (ref "U21") (pin "32") (pinfunction "C_6_32") (pintype "passive"))
    )
    (net (code "32") (name "unconnected-(U21-C_7-Pad29)") (class "Default")
      (node (ref "U21") (pin "29") (pinfunction "C_7_29") (pintype "passive"))
    )
    (net (code "33") (name "unconnected-(U21-C_8-Pad26)") (class "Default")
      (node (ref "U21") (pin "26") (pinfunction "C_8_26") (pintype "passive"))
    )
    (net (code "34") (name "unconnected-(U21-C_9-Pad23)") (class "Default")
      (node (ref "U21") (pin "23") (pinfunction "C_9_23") (pintype "passive"))
    )
    (net (code "35") (name "unconnected-(U21-C_10-Pad20)") (class "Default")
      (node (ref "U21") (pin "20") (pinfunction "C_10_20") (pintype "passive"))
    )
  )
)
